# 467444_130_3_1.net
KiCad netlist of a schematic drawn in Altium Designer
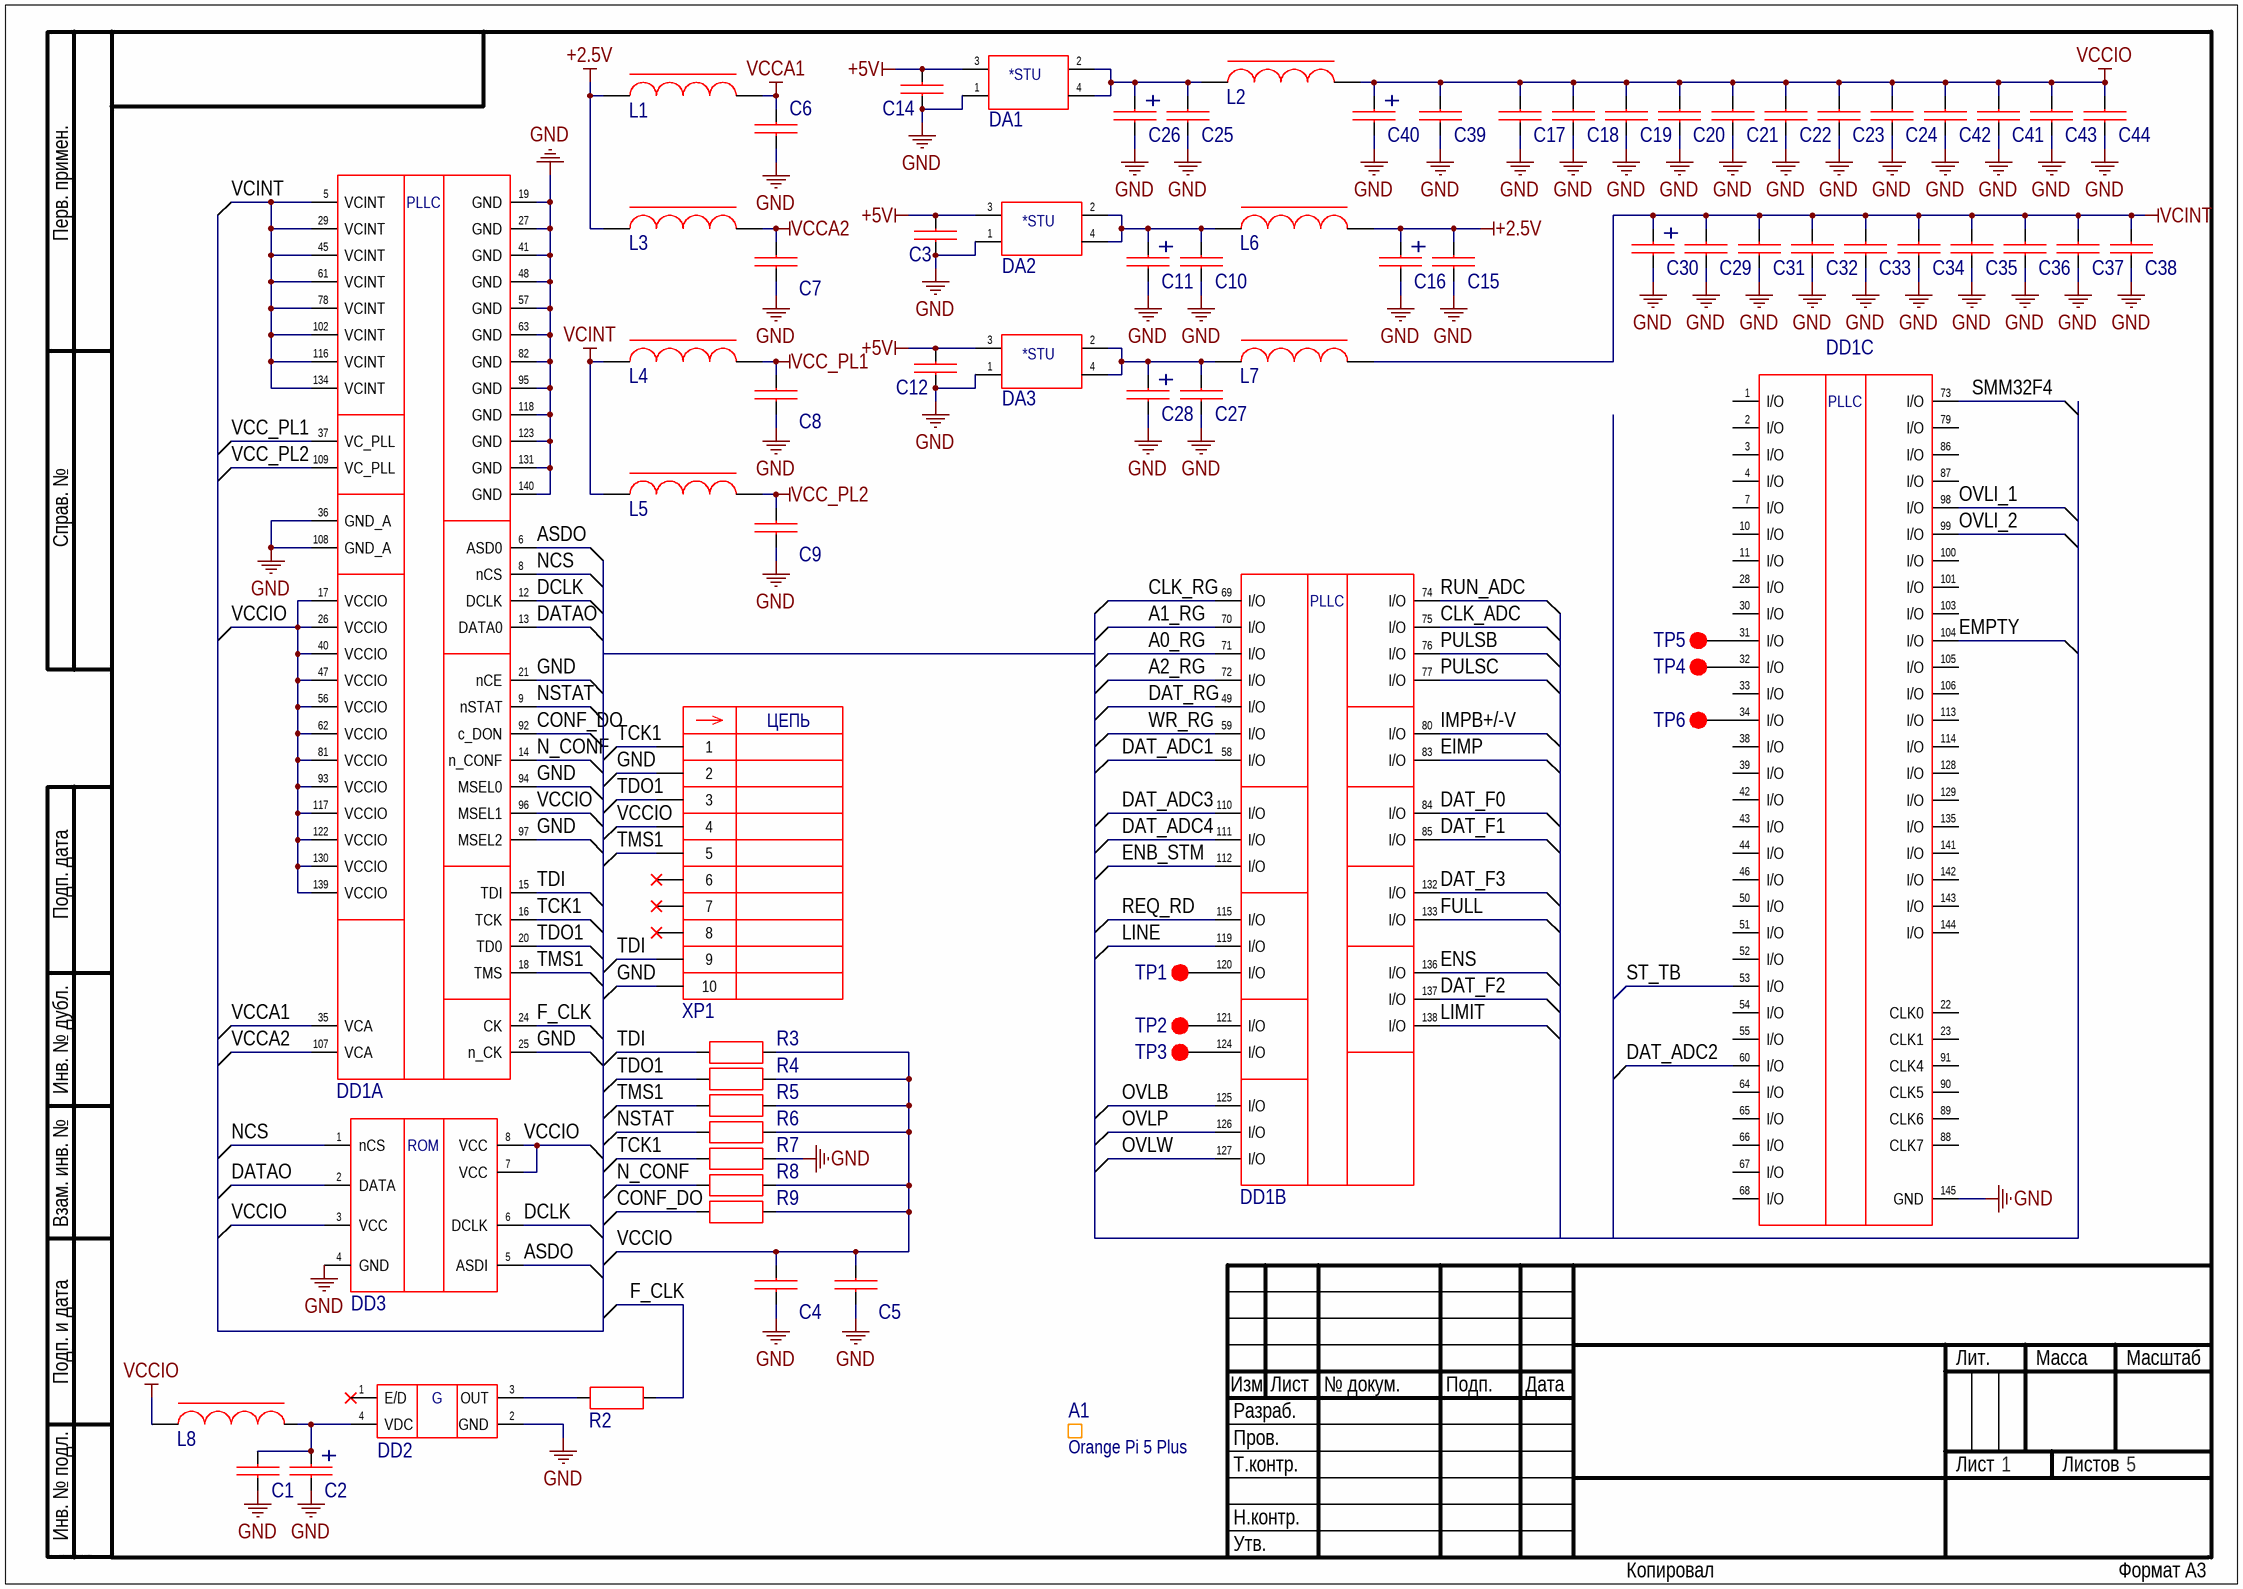
[diagram p0: УШЯИ.467444.130Э3_1.SchDoc]

(export (version "E")
  (design (tool "Eeschema 10.0.6"))
  (components
    (comp (ref "A1")
      (value "Orange Pi 5 Plus")
      (footprint "Orange_Pi_5_Plus")
      (description "8GB Rockchip RK3588, HDMI 2.1, Gigabit LAN port, USB2.0/3.0, microSD card slot, USB Type-C")
      (fields (field (name "MANUFACTURER") "Orange Pi"))
      (libsource (lib "lib") (part "0"))
    )
    (comp (ref "C1")
      (value "0,1 µF")
      (footprint "C_0805 [2012 Metric]")
      (description "Неполярный конденсатор")
      (fields (field (name "MANUFACTURER") "Murata") (field (name "VOLTAGE") "50V"))
      (libsource (lib "lib") (part "C_const"))
    )
    (comp (ref "C2")
      (value "4,7 µF")
      (footprint "C+_1210 [3528-21 Metric]")
      (description "Полярный конденсатор")
      (fields (field (name "MANUFACTURER") "KYOCERA AVX") (field (name "VOLTAGE") "20V\r\n10V"))
      (libsource (lib "lib") (part "C_electrolytic"))
    )
    (comp (ref "C3")
      (value "0,1 µF")
      (footprint "C_0805 [2012 Metric]")
      (description "Неполярный конденсатор")
      (fields (field (name "MANUFACTURER") "Murata") (field (name "VOLTAGE") "25V"))
      (libsource (lib "lib") (part "C_const"))
    )
    (comp (ref "C4")
      (value "1 µF")
      (footprint "C_0805 [2012 Metric]")
      (description "Неполярный конденсатор")
      (fields (field (name "MANUFACTURER") "Murata") (field (name "VOLTAGE") "16V"))
      (libsource (lib "lib") (part "C_const"))
    )
    (comp (ref "C5")
      (value "1 µF")
      (footprint "C_0805 [2012 Metric]")
      (description "Неполярный конденсатор")
      (fields (field (name "MANUFACTURER") "Murata") (field (name "VOLTAGE") "16V"))
      (libsource (lib "lib") (part "C_const"))
    )
    (comp (ref "C6")
      (value "0,1 µF")
      (footprint "C_0805 [2012 Metric]")
      (description "Неполярный конденсатор")
      (fields (field (name "MANUFACTURER") "Murata") (field (name "VOLTAGE") "25V"))
      (libsource (lib "lib") (part "C_const"))
    )
    (comp (ref "C7")
      (value "0,1 µF")
      (footprint "C_0805 [2012 Metric]")
      (description "Неполярный конденсатор")
      (fields (field (name "MANUFACTURER") "Murata") (field (name "VOLTAGE") "25V"))
      (libsource (lib "lib") (part "C_const"))
    )
    (comp (ref "C8")
      (value "0,1 µF")
      (footprint "C_0805 [2012 Metric]")
      (description "Неполярный конденсатор")
      (fields (field (name "MANUFACTURER") "Murata") (field (name "VOLTAGE") "25V"))
      (libsource (lib "lib") (part "C_const"))
    )
    (comp (ref "C9")
      (value "0,1 µF")
      (footprint "C_0805 [2012 Metric]")
      (description "Неполярный конденсатор")
      (fields (field (name "MANUFACTURER") "Murata") (field (name "VOLTAGE") "25V"))
      (libsource (lib "lib") (part "C_const"))
    )
    (comp (ref "C10")
      (value "0,1 µF")
      (footprint "C_0805 [2012 Metric]")
      (description "Неполярный конденсатор")
      (fields (field (name "MANUFACTURER") "Murata") (field (name "VOLTAGE") "25V"))
      (libsource (lib "lib") (part "C_const"))
    )
    (comp (ref "C11")
      (value "4,7 µF")
      (footprint "C+_1210 [3528-21 Metric]")
      (description "Полярный конденсатор")
      (fields (field (name "MANUFACTURER") "KYOCERA AVX") (field (name "VOLTAGE") "20V\r\n10V"))
      (libsource (lib "lib") (part "C_electrolytic"))
    )
    (comp (ref "C12")
      (value "0,1 µF")
      (footprint "C_0805 [2012 Metric]")
      (description "Неполярный конденсатор")
      (fields (field (name "MANUFACTURER") "Murata") (field (name "VOLTAGE") "25V"))
      (libsource (lib "lib") (part "C_const"))
    )
    (comp (ref "C14")
      (value "0,1 µF")
      (footprint "C_0805 [2012 Metric]")
      (description "Неполярный конденсатор")
      (fields (field (name "MANUFACTURER") "Murata") (field (name "VOLTAGE") "25V"))
      (libsource (lib "lib") (part "C_const"))
    )
    (comp (ref "C15")
      (value "0,1 µF")
      (footprint "C_0805 [2012 Metric]")
      (description "Неполярный конденсатор")
      (fields (field (name "MANUFACTURER") "Murata") (field (name "VOLTAGE") "25V"))
      (libsource (lib "lib") (part "C_const"))
    )
    (comp (ref "C16")
      (value "10 µF")
      (footprint "C+_1210 [3528-21 Metric]")
      (description "Полярный конденсатор")
      (fields (field (name "MANUFACTURER") "KYOCERA AVX") (field (name "VOLTAGE") "20V\r\n10V"))
      (libsource (lib "lib") (part "C_electrolytic"))
    )
    (comp (ref "C17")
      (value "0,1 µF")
      (footprint "C_0805 [2012 Metric]")
      (description "Неполярный конденсатор")
      (fields (field (name "MANUFACTURER") "Murata") (field (name "VOLTAGE") "25V"))
      (libsource (lib "lib") (part "C_const"))
    )
    (comp (ref "C18")
      (value "0,1 µF")
      (footprint "C_0805 [2012 Metric]")
      (description "Неполярный конденсатор")
      (fields (field (name "MANUFACTURER") "Murata") (field (name "VOLTAGE") "25V"))
      (libsource (lib "lib") (part "C_const"))
    )
    (comp (ref "C19")
      (value "0,1 µF")
      (footprint "C_0805 [2012 Metric]")
      (description "Неполярный конденсатор")
      (fields (field (name "MANUFACTURER") "Murata") (field (name "VOLTAGE") "25V"))
      (libsource (lib "lib") (part "C_const"))
    )
    (comp (ref "C20")
      (value "0,1 µF")
      (footprint "C_0805 [2012 Metric]")
      (description "Неполярный конденсатор")
      (fields (field (name "MANUFACTURER") "Murata") (field (name "VOLTAGE") "25V"))
      (libsource (lib "lib") (part "C_const"))
    )
    (comp (ref "C21")
      (value "0,1 µF")
      (footprint "C_0805 [2012 Metric]")
      (description "Неполярный конденсатор")
      (fields (field (name "MANUFACTURER") "Murata") (field (name "VOLTAGE") "25V"))
      (libsource (lib "lib") (part "C_const"))
    )
    (comp (ref "C22")
      (value "0,1 µF")
      (footprint "C_0805 [2012 Metric]")
      (description "Неполярный конденсатор")
      (fields (field (name "MANUFACTURER") "Murata") (field (name "VOLTAGE") "25V"))
      (libsource (lib "lib") (part "C_const"))
    )
    (comp (ref "C23")
      (value "0,1 µF")
      (footprint "C_0805 [2012 Metric]")
      (description "Неполярный конденсатор")
      (fields (field (name "MANUFACTURER") "Murata") (field (name "VOLTAGE") "25V"))
      (libsource (lib "lib") (part "C_const"))
    )
    (comp (ref "C24")
      (value "0,1 µF")
      (footprint "C_0805 [2012 Metric]")
      (description "Неполярный конденсатор")
      (fields (field (name "MANUFACTURER") "Murata") (field (name "VOLTAGE") "25V"))
      (libsource (lib "lib") (part "C_const"))
    )
    (comp (ref "C25")
      (value "0,1 µF")
      (footprint "C_0805 [2012 Metric]")
      (description "Неполярный конденсатор")
      (fields (field (name "MANUFACTURER") "Murata") (field (name "VOLTAGE") "25V"))
      (libsource (lib "lib") (part "C_const"))
    )
    (comp (ref "C26")
      (value "4,7 µF")
      (footprint "C+_1210 [3528-21 Metric]")
      (description "Полярный конденсатор")
      (fields (field (name "MANUFACTURER") "KYOCERA AVX") (field (name "VOLTAGE") "20V\r\n10V"))
      (libsource (lib "lib") (part "C_electrolytic"))
    )
    (comp (ref "C27")
      (value "0,1 µF")
      (footprint "C_0805 [2012 Metric]")
      (description "Неполярный конденсатор")
      (fields (field (name "MANUFACTURER") "Murata") (field (name "VOLTAGE") "50V"))
      (libsource (lib "lib") (part "C_const"))
    )
    (comp (ref "C28")
      (value "4,7 µF")
      (footprint "C+_1210 [3528-21 Metric]")
      (description "Полярный конденсатор")
      (fields (field (name "MANUFACTURER") "KYOCERA AVX") (field (name "VOLTAGE") "20V\r\n10V"))
      (libsource (lib "lib") (part "C_electrolytic"))
    )
    (comp (ref "C29")
      (value "0,1 µF")
      (footprint "C_0805 [2012 Metric]")
      (description "Неполярный конденсатор")
      (fields (field (name "MANUFACTURER") "Murata") (field (name "VOLTAGE") "50V"))
      (libsource (lib "lib") (part "C_const"))
    )
    (comp (ref "C30")
      (value "4,7 µF")
      (footprint "C+_1210 [3528-21 Metric]")
      (description "Полярный конденсатор")
      (fields (field (name "MANUFACTURER") "KYOCERA AVX") (field (name "VOLTAGE") "20V\r\n10V"))
      (libsource (lib "lib") (part "C_electrolytic"))
    )
    (comp (ref "C31")
      (value "0,1 µF")
      (footprint "C_0805 [2012 Metric]")
      (description "Неполярный конденсатор")
      (fields (field (name "MANUFACTURER") "Murata") (field (name "VOLTAGE") "50V"))
      (libsource (lib "lib") (part "C_const"))
    )
    (comp (ref "C32")
      (value "0,1 µF")
      (footprint "C_0805 [2012 Metric]")
      (description "Неполярный конденсатор")
      (fields (field (name "MANUFACTURER") "Murata") (field (name "VOLTAGE") "50V"))
      (libsource (lib "lib") (part "C_const"))
    )
    (comp (ref "C33")
      (value "0,1 µF")
      (footprint "C_0805 [2012 Metric]")
      (description "Неполярный конденсатор")
      (fields (field (name "MANUFACTURER") "Murata") (field (name "VOLTAGE") "50V"))
      (libsource (lib "lib") (part "C_const"))
    )
    (comp (ref "C34")
      (value "0,1 µF")
      (footprint "C_0805 [2012 Metric]")
      (description "Неполярный конденсатор")
      (fields (field (name "MANUFACTURER") "Murata") (field (name "VOLTAGE") "50V"))
      (libsource (lib "lib") (part "C_const"))
    )
    (comp (ref "C35")
      (value "0,1 µF")
      (footprint "C_0805 [2012 Metric]")
      (description "Неполярный конденсатор")
      (fields (field (name "MANUFACTURER") "Murata") (field (name "VOLTAGE") "50V"))
      (libsource (lib "lib") (part "C_const"))
    )
    (comp (ref "C36")
      (value "0,1 µF")
      (footprint "C_0805 [2012 Metric]")
      (description "Неполярный конденсатор")
      (fields (field (name "MANUFACTURER") "Murata") (field (name "VOLTAGE") "50V"))
      (libsource (lib "lib") (part "C_const"))
    )
    (comp (ref "C37")
      (value "0,1 µF")
      (footprint "C_0805 [2012 Metric]")
      (description "Неполярный конденсатор")
      (fields (field (name "MANUFACTURER") "Murata") (field (name "VOLTAGE") "50V"))
      (libsource (lib "lib") (part "C_const"))
    )
    (comp (ref "C38")
      (value "0,1 µF")
      (footprint "C_0805 [2012 Metric]")
      (description "Неполярный конденсатор")
      (fields (field (name "MANUFACTURER") "Murata") (field (name "VOLTAGE") "50V"))
      (libsource (lib "lib") (part "C_const"))
    )
    (comp (ref "C39")
      (value "0,1 µF")
      (footprint "C_0805 [2012 Metric]")
      (description "Неполярный конденсатор")
      (fields (field (name "MANUFACTURER") "Murata") (field (name "VOLTAGE") "50V"))
      (libsource (lib "lib") (part "C_const"))
    )
    (comp (ref "C40")
      (value "10 µF")
      (footprint "C+_1210 [3528-21 Metric]")
      (description "Полярный конденсатор")
      (fields (field (name "MANUFACTURER") "KYOCERA AVX") (field (name "VOLTAGE") "20V\r\n10V"))
      (libsource (lib "lib") (part "C_electrolytic"))
    )
    (comp (ref "C41")
      (value "0,1 µF")
      (footprint "C_0805 [2012 Metric]")
      (description "Неполярный конденсатор")
      (fields (field (name "MANUFACTURER") "Murata") (field (name "VOLTAGE") "50V"))
      (libsource (lib "lib") (part "C_const"))
    )
    (comp (ref "C42")
      (value "0,1 µF")
      (footprint "C_0805 [2012 Metric]")
      (description "Неполярный конденсатор")
      (fields (field (name "MANUFACTURER") "Murata") (field (name "VOLTAGE") "50V"))
      (libsource (lib "lib") (part "C_const"))
    )
    (comp (ref "C43")
      (value "0,1 µF")
      (footprint "C_0805 [2012 Metric]")
      (description "Неполярный конденсатор")
      (fields (field (name "MANUFACTURER") "Murata") (field (name "VOLTAGE") "50V"))
      (libsource (lib "lib") (part "C_const"))
    )
    (comp (ref "C44")
      (value "0,1 µF")
      (footprint "C_0805 [2012 Metric]")
      (description "Неполярный конденсатор")
      (fields (field (name "MANUFACTURER") "Murata") (field (name "VOLTAGE") "50V"))
      (libsource (lib "lib") (part "C_const"))
    )
    (comp (ref "DA1")
      (value "LD1117AS33TR")
      (footprint "SOT-223")
      (description "IC, Fixed LDO Voltage Regulator, 5.3V to 10V, 1.15V Dropout, 3.3Vout, 1Aout")
      (fields (field (name "MANUFACTURER") "STMicroelectronics"))
      (libsource (lib "lib") (part "VolReg_LD1117AS33TR"))
    )
    (comp (ref "DA2")
      (value "LD1117AS25TR")
      (footprint "SOT-223")
      (description "IC, Linear Voltage Regulator, 1 Output, 1V Dropout, 2.5Vout, 1Aout")
      (fields (field (name "MANUFACTURER") "STMicroelectronics"))
      (libsource (lib "lib") (part "VolReg_LD1117AS33TR"))
    )
    (comp (ref "DA3")
      (value "LD1117AS12TR")
      (footprint "SOT-223")
      (description "IC, Fixed LDO Voltage Regulator, 1 Output, 1V Dropout, 1.2Vout, 1Aout")
      (fields (field (name "MANUFACTURER") "STMicroelectronics"))
      (libsource (lib "lib") (part "VolReg_LD1117AS33TR"))
    )
    (comp (ref "DD1")
      (value "EP3C5E144I7")
      (footprint "EQFP-144[20x20]_0.5_22x22x1.6")
      (description "IC, Cyclone III, Field Programmable Gate Array (FPGA), 	1.15V to 1.25V, 315 MHz, 94 I/O")
      (fields (field (name "MANUFACTURER") "Intel"))
      (libsource (lib "lib") (part "EP3C5E144I7"))
    )
    (comp (ref "DD2")
      (value "O 20,0-JO32-B-3.3-1-T1-LF")
      (footprint "JO32")
      (description "Crystals, Oscillators, 20 MHz")
      (fields (field (name "MANUFACTURER") "Jauch Quartz GmbH"))
      (libsource (lib "lib") (part "JO32"))
    )
    (comp (ref "DD3")
      (value "EPCS4SI8N")
      (footprint "SOIC-8_1.27_5x4x1.75")
      (description "IC, FPGA Configuration Memory, Flash, 4 Mbit, 40 MHz, JTAG, Serial")
      (fields (field (name "MANUFACTURER") "Intel"))
      (libsource (lib "lib") (part "EPCS4"))
    )
    (comp (ref "L1")
      (value "0,22 μH")
      (footprint "IND_LQH31CN")
      (fields (field (name "MANUFACTURER") "Murata") (field (name "TOLERANCE") "±20%"))
      (libsource (lib "lib") (part "IND_ferromagnetic/ferrite_core"))
    )
    (comp (ref "L2")
      (value "~")
      (footprint "IND_0805 [2012 Metric]")
      (fields (field (name "MANUFACTURER") "Vishay") (field (name "TOLERANCE") "±25%"))
      (libsource (lib "lib") (part "IND_ferromagnetic/ferrite_core"))
    )
    (comp (ref "L3")
      (value "0,22 μH")
      (footprint "IND_LQH31CN")
      (fields (field (name "MANUFACTURER") "Murata") (field (name "TOLERANCE") "±20%"))
      (libsource (lib "lib") (part "IND_ferromagnetic/ferrite_core"))
    )
    (comp (ref "L4")
      (value "0,22 μH")
      (footprint "IND_LQH31CN")
      (fields (field (name "MANUFACTURER") "Murata") (field (name "TOLERANCE") "±20%"))
      (libsource (lib "lib") (part "IND_ferromagnetic/ferrite_core"))
    )
    (comp (ref "L5")
      (value "0,22 μH")
      (footprint "IND_LQH31CN")
      (fields (field (name "MANUFACTURER") "Murata") (field (name "TOLERANCE") "±20%"))
      (libsource (lib "lib") (part "IND_ferromagnetic/ferrite_core"))
    )
    (comp (ref "L6")
      (value "~")
      (footprint "IND_0805 [2012 Metric]")
      (fields (field (name "MANUFACTURER") "Vishay") (field (name "TOLERANCE") "±25%"))
      (libsource (lib "lib") (part "IND_ferromagnetic/ferrite_core"))
    )
    (comp (ref "L7")
      (value "~")
      (footprint "IND_0805 [2012 Metric]")
      (fields (field (name "MANUFACTURER") "Vishay") (field (name "TOLERANCE") "±25%"))
      (libsource (lib "lib") (part "IND_ferromagnetic/ferrite_core"))
    )
    (comp (ref "L8")
      (value "~")
      (footprint "IND_0805 [2012 Metric]")
      (fields (field (name "MANUFACTURER") "Vishay") (field (name "TOLERANCE") "±25%"))
      (libsource (lib "lib") (part "IND_ferromagnetic/ferrite_core"))
    )
    (comp (ref "R2")
      (value "51R")
      (footprint "R_0805 [2012 Metric]")
      (fields (field (name "TOLERANCE") "±5%"))
      (libsource (lib "lib") (part "R_Const"))
    )
    (comp (ref "R3")
      (value "1k")
      (footprint "R_0805 [2012 Metric]")
      (fields (field (name "TOLERANCE") "±5%"))
      (libsource (lib "lib") (part "R_Const"))
    )
    (comp (ref "R4")
      (value "10k")
      (footprint "R_0805 [2012 Metric]")
      (fields (field (name "TOLERANCE") "±5%"))
      (libsource (lib "lib") (part "R_Const"))
    )
    (comp (ref "R5")
      (value "1k")
      (footprint "R_0805 [2012 Metric]")
      (fields (field (name "TOLERANCE") "±5%"))
      (libsource (lib "lib") (part "R_Const"))
    )
    (comp (ref "R6")
      (value "10k")
      (footprint "R_0805 [2012 Metric]")
      (fields (field (name "TOLERANCE") "±5%"))
      (libsource (lib "lib") (part "R_Const"))
    )
    (comp (ref "R7")
      (value "1k")
      (footprint "R_0805 [2012 Metric]")
      (fields (field (name "TOLERANCE") "±5%"))
      (libsource (lib "lib") (part "R_Const"))
    )
    (comp (ref "R8")
      (value "10k")
      (footprint "R_0805 [2012 Metric]")
      (fields (field (name "TOLERANCE") "±5%"))
      (libsource (lib "lib") (part "R_Const"))
    )
    (comp (ref "R9")
      (value "10k")
      (footprint "R_0805 [2012 Metric]")
      (fields (field (name "TOLERANCE") "±5%"))
      (libsource (lib "lib") (part "R_Const"))
    )
    (comp (ref "TP1") (value "~") (footprint "DSP_1.3") (libsource (lib "lib") (part "TP")))
    (comp (ref "TP2") (value "~") (footprint "DSP_1.3") (libsource (lib "lib") (part "TP")))
    (comp (ref "TP3") (value "~") (footprint "DSP_1.3") (libsource (lib "lib") (part "TP")))
    (comp (ref "TP4") (value "~") (footprint "DSP_1.3") (libsource (lib "lib") (part "TP")))
    (comp (ref "TP5") (value "~") (footprint "DSP_1.3") (libsource (lib "lib") (part "TP")))
    (comp (ref "TP6") (value "~") (footprint "DSP_1.3") (libsource (lib "lib") (part "TP")))
    (comp (ref "XP1")
      (value "PLD-10")
      (footprint "PLD-10")
      (description "Male, 10 pins, 2 rows, Vertical")
      (fields (field (name "MANUFACTURER") "Connfly electronic"))
      (libsource (lib "lib") (part "M_10"))
    )
  )
  (nets
    (net (code "1") (name "+2.5V") (class "Default")
      (node (ref "C15") (pin "2") (pinfunction "2_2") (pintype "passive"))
      (node (ref "C16") (pin "+") (pinfunction "+_+") (pintype "passive"))
      (node (ref "L1") (pin "1") (pinfunction "1_1") (pintype "passive"))
      (node (ref "L3") (pin "1") (pinfunction "1_1") (pintype "passive"))
      (node (ref "L6") (pin "2") (pinfunction "2_2") (pintype "passive"))
    )
    (net (code "2") (name "+5V") (class "Default")
      (node (ref "C12") (pin "2") (pinfunction "2_2") (pintype "passive"))
      (node (ref "C14") (pin "2") (pinfunction "2_2") (pintype "passive"))
      (node (ref "C3") (pin "2") (pinfunction "2_2") (pintype "passive"))
      (node (ref "DA1") (pin "3") (pinfunction "VIN_3") (pintype "passive"))
      (node (ref "DA2") (pin "3") (pinfunction "VIN_3") (pintype "passive"))
      (node (ref "DA3") (pin "3") (pinfunction "VIN_3") (pintype "passive"))
    )
    (net (code "3") (name "/A0_RG") (class "Default")
      (node (ref "DD1") (pin "71") (pinfunction "I/O_71") (pintype "passive"))
    )
    (net (code "4") (name "/A1_RG") (class "Default")
      (node (ref "DD1") (pin "70") (pinfunction "I/O_70") (pintype "passive"))
    )
    (net (code "5") (name "/A2_RG") (class "Default")
      (node (ref "DD1") (pin "72") (pinfunction "I/O_72") (pintype "passive"))
    )
    (net (code "6") (name "/ASDO") (class "Default")
      (node (ref "DD1") (pin "6") (pinfunction "ASD0_6") (pintype "passive"))
      (node (ref "DD3") (pin "5") (pinfunction "ASDI_5") (pintype "passive"))
    )
    (net (code "7") (name "/CLK_ADC") (class "Default")
      (node (ref "DD1") (pin "75") (pinfunction "I/O_75") (pintype "passive"))
    )
    (net (code "8") (name "/CLK_RG") (class "Default")
      (node (ref "DD1") (pin "69") (pinfunction "I/O_69") (pintype "passive"))
    )
    (net (code "9") (name "/CONF_DO") (class "Default")
      (node (ref "DD1") (pin "92") (pinfunction "c_DON_92") (pintype "passive"))
      (node (ref "R9") (pin "1") (pinfunction "1_1") (pintype "passive"))
    )
    (net (code "10") (name "/DATAO") (class "Default")
      (node (ref "DD1") (pin "13") (pinfunction "DATA0_13") (pintype "passive"))
      (node (ref "DD3") (pin "2") (pinfunction "DATA_2") (pintype "passive"))
    )
    (net (code "11") (name "/DAT_ADC1") (class "Default")
      (node (ref "DD1") (pin "58") (pinfunction "I/O_58") (pintype "passive"))
    )
    (net (code "12") (name "/DAT_ADC2") (class "Default")
      (node (ref "DD1") (pin "60") (pinfunction "I/O_60") (pintype "passive"))
    )
    (net (code "13") (name "/DAT_ADC3") (class "Default")
      (node (ref "DD1") (pin "110") (pinfunction "I/O_110") (pintype "passive"))
    )
    (net (code "14") (name "/DAT_ADC4") (class "Default")
      (node (ref "DD1") (pin "111") (pinfunction "I/O_111") (pintype "passive"))
    )
    (net (code "15") (name "/DAT_F0") (class "Default")
      (node (ref "DD1") (pin "84") (pinfunction "I/O_84") (pintype "passive"))
    )
    (net (code "16") (name "/DAT_F1") (class "Default")
      (node (ref "DD1") (pin "85") (pinfunction "I/O_85") (pintype "passive"))
    )
    (net (code "17") (name "/DAT_F2") (class "Default")
      (node (ref "DD1") (pin "137") (pinfunction "I/O_137") (pintype "passive"))
    )
    (net (code "18") (name "/DAT_F3") (class "Default")
      (node (ref "DD1") (pin "132") (pinfunction "I/O_132") (pintype "passive"))
    )
    (net (code "19") (name "/DAT_RG") (class "Default")
      (node (ref "DD1") (pin "49") (pinfunction "I/O_49") (pintype "passive"))
    )
    (net (code "20") (name "/DCLK") (class "Default")
      (node (ref "DD1") (pin "12") (pinfunction "DCLK_12") (pintype "passive"))
      (node (ref "DD3") (pin "6") (pinfunction "DCLK_6") (pintype "passive"))
    )
    (net (code "21") (name "/EIMP") (class "Default")
      (node (ref "DD1") (pin "83") (pinfunction "I/O_83") (pintype "passive"))
    )
    (net (code "22") (name "/EMPTY") (class "Default")
      (node (ref "DD1") (pin "104") (pinfunction "I/O_104") (pintype "passive"))
    )
    (net (code "23") (name "/ENB_STM") (class "Default")
      (node (ref "DD1") (pin "112") (pinfunction "I/O_112") (pintype "passive"))
    )
    (net (code "24") (name "/ENS") (class "Default")
      (node (ref "DD1") (pin "136") (pinfunction "I/O_136") (pintype "passive"))
    )
    (net (code "25") (name "/FULL") (class "Default")
      (node (ref "DD1") (pin "133") (pinfunction "I/O_133") (pintype "passive"))
    )
    (net (code "26") (name "/F_CLK") (class "Default")
      (node (ref "DD1") (pin "24") (pinfunction "CK_24") (pintype "passive"))
      (node (ref "R2") (pin "2") (pinfunction "2_2") (pintype "passive"))
    )
    (net (code "27") (name "/IMPB+{slash}-V") (class "Default")
      (node (ref "DD1") (pin "80") (pinfunction "I/O_80") (pintype "passive"))
    )
    (net (code "28") (name "/LIMIT") (class "Default")
      (node (ref "DD1") (pin "138") (pinfunction "I/O_138") (pintype "passive"))
    )
    (net (code "29") (name "/LINE") (class "Default")
      (node (ref "DD1") (pin "119") (pinfunction "I/O_119") (pintype "passive"))
    )
    (net (code "30") (name "/NCS") (class "Default")
      (node (ref "DD1") (pin "8") (pinfunction "nCS_8") (pintype "passive"))
      (node (ref "DD3") (pin "1") (pinfunction "nCS_1") (pintype "passive"))
    )
    (net (code "31") (name "/NSTAT") (class "Default")
      (node (ref "DD1") (pin "9") (pinfunction "nSTAT_9") (pintype "passive"))
      (node (ref "R6") (pin "1") (pinfunction "1_1") (pintype "passive"))
    )
    (net (code "32") (name "/N_CONF") (class "Default")
      (node (ref "DD1") (pin "14") (pinfunction "n_CONF_14") (pintype "passive"))
      (node (ref "R8") (pin "1") (pinfunction "1_1") (pintype "passive"))
    )
    (net (code "33") (name "/OVLB") (class "Default")
      (node (ref "DD1") (pin "125") (pinfunction "I/O_125") (pintype "passive"))
    )
    (net (code "34") (name "/OVLI_1") (class "Default")
      (node (ref "DD1") (pin "98") (pinfunction "I/O_98") (pintype "passive"))
    )
    (net (code "35") (name "/OVLI_2") (class "Default")
      (node (ref "DD1") (pin "99") (pinfunction "I/O_99") (pintype "passive"))
    )
    (net (code "36") (name "/OVLP") (class "Default")
      (node (ref "DD1") (pin "126") (pinfunction "I/O_126") (pintype "passive"))
    )
    (net (code "37") (name "/OVLW") (class "Default")
      (node (ref "DD1") (pin "127") (pinfunction "I/O_127") (pintype "passive"))
    )
    (net (code "38") (name "/PULSB") (class "Default")
      (node (ref "DD1") (pin "76") (pinfunction "I/O_76") (pintype "passive"))
    )
    (net (code "39") (name "/PULSC") (class "Default")
      (node (ref "DD1") (pin "77") (pinfunction "I/O_77") (pintype "passive"))
    )
    (net (code "40") (name "/REQ_RD") (class "Default")
      (node (ref "DD1") (pin "115") (pinfunction "I/O_115") (pintype "passive"))
    )
    (net (code "41") (name "/RUN_ADC") (class "Default")
      (node (ref "DD1") (pin "74") (pinfunction "I/O_74") (pintype "passive"))
    )
    (net (code "42") (name "/SMM32F4") (class "Default")
      (node (ref "DD1") (pin "73") (pinfunction "I/O_73") (pintype "passive"))
    )
    (net (code "43") (name "/ST_TB") (class "Default")
      (node (ref "DD1") (pin "53") (pinfunction "I/O_53") (pintype "passive"))
    )
    (net (code "44") (name "/TCK1") (class "Default")
      (node (ref "DD1") (pin "16") (pinfunction "TCK_16") (pintype "passive"))
      (node (ref "R7") (pin "1") (pinfunction "1_1") (pintype "passive"))
      (node (ref "XP1") (pin "1") (pinfunction "1_1") (pintype "passive"))
    )
    (net (code "45") (name "/TDI") (class "Default")
      (node (ref "DD1") (pin "15") (pinfunction "TDI_15") (pintype "passive"))
      (node (ref "R3") (pin "1") (pinfunction "1_1") (pintype "passive"))
      (node (ref "XP1") (pin "9") (pinfunction "9_9") (pintype "passive"))
    )
    (net (code "46") (name "/TDO1") (class "Default")
      (node (ref "DD1") (pin "20") (pinfunction "TD0_20") (pintype "passive"))
      (node (ref "R4") (pin "1") (pinfunction "1_1") (pintype "passive"))
      (node (ref "XP1") (pin "3") (pinfunction "3_3") (pintype "passive"))
    )
    (net (code "47") (name "/TMS1") (class "Default")
      (node (ref "DD1") (pin "18") (pinfunction "TMS_18") (pintype "passive"))
      (node (ref "R5") (pin "1") (pinfunction "1_1") (pintype "passive"))
      (node (ref "XP1") (pin "5") (pinfunction "5_5") (pintype "passive"))
    )
    (net (code "48") (name "/WR_RG") (class "Default")
      (node (ref "DD1") (pin "59") (pinfunction "I/O_59") (pintype "passive"))
    )
    (net (code "49") (name "GND") (class "Default")
      (node (ref "C1") (pin "1") (pinfunction "1_1") (pintype "passive"))
      (node (ref "C10") (pin "1") (pinfunction "1_1") (pintype "passive"))
      (node (ref "C11") (pin "-") (pinfunction "-_-") (pintype "passive"))
      (node (ref "C12") (pin "1") (pinfunction "1_1") (pintype "passive"))
      (node (ref "C14") (pin "1") (pinfunction "1_1") (pintype "passive"))
      (node (ref "C15") (pin "1") (pinfunction "1_1") (pintype "passive"))
      (node (ref "C16") (pin "-") (pinfunction "-_-") (pintype "passive"))
      (node (ref "C17") (pin "1") (pinfunction "1_1") (pintype "passive"))
      (node (ref "C18") (pin "1") (pinfunction "1_1") (pintype "passive"))
      (node (ref "C19") (pin "1") (pinfunction "1_1") (pintype "passive"))
      (node (ref "C2") (pin "-") (pinfunction "-_-") (pintype "passive"))
      (node (ref "C20") (pin "1") (pinfunction "1_1") (pintype "passive"))
      (node (ref "C21") (pin "1") (pinfunction "1_1") (pintype "passive"))
      (node (ref "C22") (pin "1") (pinfunction "1_1") (pintype "passive"))
      (node (ref "C23") (pin "1") (pinfunction "1_1") (pintype "passive"))
      (node (ref "C24") (pin "1") (pinfunction "1_1") (pintype "passive"))
      (node (ref "C25") (pin "1") (pinfunction "1_1") (pintype "passive"))
      (node (ref "C26") (pin "-") (pinfunction "-_-") (pintype "passive"))
      (node (ref "C27") (pin "1") (pinfunction "1_1") (pintype "passive"))
      (node (ref "C28") (pin "-") (pinfunction "-_-") (pintype "passive"))
      (node (ref "C29") (pin "1") (pinfunction "1_1") (pintype "passive"))
      (node (ref "C3") (pin "1") (pinfunction "1_1") (pintype "passive"))
      (node (ref "C30") (pin "-") (pinfunction "-_-") (pintype "passive"))
      (node (ref "C31") (pin "1") (pinfunction "1_1") (pintype "passive"))
      (node (ref "C32") (pin "1") (pinfunction "1_1") (pintype "passive"))
      (node (ref "C33") (pin "1") (pinfunction "1_1") (pintype "passive"))
      (node (ref "C34") (pin "1") (pinfunction "1_1") (pintype "passive"))
      (node (ref "C35") (pin "1") (pinfunction "1_1") (pintype "passive"))
      (node (ref "C36") (pin "1") (pinfunction "1_1") (pintype "passive"))
      (node (ref "C37") (pin "1") (pinfunction "1_1") (pintype "passive"))
      (node (ref "C38") (pin "1") (pinfunction "1_1") (pintype "passive"))
      (node (ref "C39") (pin "1") (pinfunction "1_1") (pintype "passive"))
      (node (ref "C4") (pin "1") (pinfunction "1_1") (pintype "passive"))
      (node (ref "C40") (pin "-") (pinfunction "-_-") (pintype "passive"))
      (node (ref "C41") (pin "1") (pinfunction "1_1") (pintype "passive"))
      (node (ref "C42") (pin "1") (pinfunction "1_1") (pintype "passive"))
      (node (ref "C43") (pin "1") (pinfunction "1_1") (pintype "passive"))
      (node (ref "C44") (pin "1") (pinfunction "1_1") (pintype "passive"))
      (node (ref "C5") (pin "1") (pinfunction "1_1") (pintype "passive"))
      (node (ref "C6") (pin "1") (pinfunction "1_1") (pintype "passive"))
      (node (ref "C7") (pin "1") (pinfunction "1_1") (pintype "passive"))
      (node (ref "C8") (pin "1") (pinfunction "1_1") (pintype "passive"))
      (node (ref "C9") (pin "1") (pinfunction "1_1") (pintype "passive"))
      (node (ref "DA1") (pin "1") (pinfunction "ADJ/GND_1") (pintype "passive"))
      (node (ref "DA2") (pin "1") (pinfunction "ADJ/GND_1") (pintype "passive"))
      (node (ref "DA3") (pin "1") (pinfunction "ADJ/GND_1") (pintype "passive"))
      (node (ref "DD1") (pin "108") (pinfunction "GND_A_108") (pintype "passive"))
      (node (ref "DD1") (pin "118") (pinfunction "GND_118") (pintype "passive"))
      (node (ref "DD1") (pin "123") (pinfunction "GND_123") (pintype "passive"))
      (node (ref "DD1") (pin "131") (pinfunction "GND_131") (pintype "passive"))
      (node (ref "DD1") (pin "140") (pinfunction "GND_140") (pintype "passive"))
      (node (ref "DD1") (pin "145") (pinfunction "GND_145") (pintype "passive"))
      (node (ref "DD1") (pin "19") (pinfunction "GND_19") (pintype "passive"))
      (node (ref "DD1") (pin "21") (pinfunction "nCE_21") (pintype "passive"))
      (node (ref "DD1") (pin "25") (pinfunction "n_CK_25") (pintype "passive"))
      (node (ref "DD1") (pin "27") (pinfunction "GND_27") (pintype "passive"))
      (node (ref "DD1") (pin "36") (pinfunction "GND_A_36") (pintype "passive"))
      (node (ref "DD1") (pin "41") (pinfunction "GND_41") (pintype "passive"))
      (node (ref "DD1") (pin "48") (pinfunction "GND_48") (pintype "passive"))
      (node (ref "DD1") (pin "57") (pinfunction "GND_57") (pintype "passive"))
      (node (ref "DD1") (pin "63") (pinfunction "GND_63") (pintype "passive"))
      (node (ref "DD1") (pin "82") (pinfunction "GND_82") (pintype "passive"))
      (node (ref "DD1") (pin "94") (pinfunction "MSEL0_94") (pintype "passive"))
      (node (ref "DD1") (pin "95") (pinfunction "GND_95") (pintype "passive"))
      (node (ref "DD1") (pin "97") (pinfunction "MSEL2_97") (pintype "passive"))
      (node (ref "DD2") (pin "2") (pinfunction "GND_2") (pintype "passive"))
      (node (ref "DD3") (pin "4") (pinfunction "GND_4") (pintype "passive"))
      (node (ref "R7") (pin "2") (pinfunction "2_2") (pintype "passive"))
      (node (ref "XP1") (pin "10") (pinfunction "10_10") (pintype "passive"))
      (node (ref "XP1") (pin "2") (pinfunction "2_2") (pintype "passive"))
    )
    (net (code "50") (name "Net-(C10-Pad2)") (class "Default")
      (node (ref "C10") (pin "2") (pinfunction "2_2") (pintype "passive"))
      (node (ref "C11") (pin "+") (pinfunction "+_+") (pintype "passive"))
      (node (ref "DA2") (pin "2") (pinfunction "VOUT_2") (pintype "passive"))
      (node (ref "DA2") (pin "4") (pinfunction "VOUT_4") (pintype "passive"))
      (node (ref "L6") (pin "1") (pinfunction "1_1") (pintype "passive"))
    )
    (net (code "51") (name "Net-(C25-Pad2)") (class "Default")
      (node (ref "C25") (pin "2") (pinfunction "2_2") (pintype "passive"))
      (node (ref "C26") (pin "+") (pinfunction "+_+") (pintype "passive"))
      (node (ref "DA1") (pin "2") (pinfunction "VOUT_2") (pintype "passive"))
      (node (ref "DA1") (pin "4") (pinfunction "VOUT_4") (pintype "passive"))
      (node (ref "L2") (pin "1") (pinfunction "1_1") (pintype "passive"))
    )
    (net (code "52") (name "Net-(C27-Pad2)") (class "Default")
      (node (ref "C27") (pin "2") (pinfunction "2_2") (pintype "passive"))
      (node (ref "C28") (pin "+") (pinfunction "+_+") (pintype "passive"))
      (node (ref "DA3") (pin "2") (pinfunction "VOUT_2") (pintype "passive"))
      (node (ref "DA3") (pin "4") (pinfunction "VOUT_4") (pintype "passive"))
      (node (ref "L7") (pin "1") (pinfunction "1_1") (pintype "passive"))
    )
    (net (code "53") (name "Net-(DD1B-I{slash}O-Pad120)") (class "Default")
      (node (ref "DD1") (pin "120") (pinfunction "I/O_120") (pintype "passive"))
      (node (ref "TP1") (pin "1") (pinfunction "1_1") (pintype "passive"))
    )
    (net (code "54") (name "Net-(DD1B-I{slash}O-Pad121)") (class "Default")
      (node (ref "DD1") (pin "121") (pinfunction "I/O_121") (pintype "passive"))
      (node (ref "TP2") (pin "1") (pinfunction "1_1") (pintype "passive"))
    )
    (net (code "55") (name "Net-(DD1B-I{slash}O-Pad124)") (class "Default")
      (node (ref "DD1") (pin "124") (pinfunction "I/O_124") (pintype "passive"))
      (node (ref "TP3") (pin "1") (pinfunction "1_1") (pintype "passive"))
    )
    (net (code "56") (name "Net-(DD1C-I{slash}O-Pad31)") (class "Default")
      (node (ref "DD1") (pin "31") (pinfunction "I/O_31") (pintype "passive"))
      (node (ref "TP5") (pin "1") (pinfunction "1_1") (pintype "passive"))
    )
    (net (code "57") (name "Net-(DD1C-I{slash}O-Pad32)") (class "Default")
      (node (ref "DD1") (pin "32") (pinfunction "I/O_32") (pintype "passive"))
      (node (ref "TP4") (pin "1") (pinfunction "1_1") (pintype "passive"))
    )
    (net (code "58") (name "Net-(DD1C-I{slash}O-Pad34)") (class "Default")
      (node (ref "DD1") (pin "34") (pinfunction "I/O_34") (pintype "passive"))
      (node (ref "TP6") (pin "1") (pinfunction "1_1") (pintype "passive"))
    )
    (net (code "59") (name "Net-(DD2-OUT)") (class "Default")
      (node (ref "DD2") (pin "3") (pinfunction "OUT_3") (pintype "passive"))
      (node (ref "R2") (pin "1") (pinfunction "1_1") (pintype "passive"))
    )
    (net (code "60") (name "Net-(DD2-VDC)") (class "Default")
      (node (ref "C1") (pin "2") (pinfunction "2_2") (pintype "passive"))
      (node (ref "C2") (pin "+") (pinfunction "+_+") (pintype "passive"))
      (node (ref "DD2") (pin "4") (pinfunction "VDC_4") (pintype "passive"))
      (node (ref "L8") (pin "2") (pinfunction "2_2") (pintype "passive"))
    )
    (net (code "61") (name "VCCA1") (class "Default")
      (node (ref "C6") (pin "2") (pinfunction "2_2") (pintype "passive"))
      (node (ref "DD1") (pin "35") (pinfunction "VCA_35") (pintype "passive"))
      (node (ref "L1") (pin "2") (pinfunction "2_2") (pintype "passive"))
    )
    (net (code "62") (name "VCCA2") (class "Default")
      (node (ref "C7") (pin "2") (pinfunction "2_2") (pintype "passive"))
      (node (ref "DD1") (pin "107") (pinfunction "VCA_107") (pintype "passive"))
      (node (ref "L3") (pin "2") (pinfunction "2_2") (pintype "passive"))
    )
    (net (code "63") (name "VCCIO") (class "Default")
      (node (ref "C17") (pin "2") (pinfunction "2_2") (pintype "passive"))
      (node (ref "C18") (pin "2") (pinfunction "2_2") (pintype "passive"))
      (node (ref "C19") (pin "2") (pinfunction "2_2") (pintype "passive"))
      (node (ref "C20") (pin "2") (pinfunction "2_2") (pintype "passive"))
      (node (ref "C21") (pin "2") (pinfunction "2_2") (pintype "passive"))
      (node (ref "C22") (pin "2") (pinfunction "2_2") (pintype "passive"))
      (node (ref "C23") (pin "2") (pinfunction "2_2") (pintype "passive"))
      (node (ref "C24") (pin "2") (pinfunction "2_2") (pintype "passive"))
      (node (ref "C39") (pin "2") (pinfunction "2_2") (pintype "passive"))
      (node (ref "C4") (pin "2") (pinfunction "2_2") (pintype "passive"))
      (node (ref "C40") (pin "+") (pinfunction "+_+") (pintype "passive"))
      (node (ref "C41") (pin "2") (pinfunction "2_2") (pintype "passive"))
      (node (ref "C42") (pin "2") (pinfunction "2_2") (pintype "passive"))
      (node (ref "C43") (pin "2") (pinfunction "2_2") (pintype "passive"))
      (node (ref "C44") (pin "2") (pinfunction "2_2") (pintype "passive"))
      (node (ref "C5") (pin "2") (pinfunction "2_2") (pintype "passive"))
      (node (ref "DD1") (pin "117") (pinfunction "VCCIO_117") (pintype "passive"))
      (node (ref "DD1") (pin "122") (pinfunction "VCCIO_122") (pintype "passive"))
      (node (ref "DD1") (pin "130") (pinfunction "VCCIO_130") (pintype "passive"))
      (node (ref "DD1") (pin "139") (pinfunction "VCCIO_139") (pintype "passive"))
      (node (ref "DD1") (pin "17") (pinfunction "VCCIO_17") (pintype "passive"))
      (node (ref "DD1") (pin "26") (pinfunction "VCCIO_26") (pintype "passive"))
      (node (ref "DD1") (pin "40") (pinfunction "VCCIO_40") (pintype "passive"))
      (node (ref "DD1") (pin "47") (pinfunction "VCCIO_47") (pintype "passive"))
      (node (ref "DD1") (pin "56") (pinfunction "VCCIO_56") (pintype "passive"))
      (node (ref "DD1") (pin "62") (pinfunction "VCCIO_62") (pintype "passive"))
      (node (ref "DD1") (pin "81") (pinfunction "VCCIO_81") (pintype "passive"))
      (node (ref "DD1") (pin "93") (pinfunction "VCCIO_93") (pintype "passive"))
      (node (ref "DD1") (pin "96") (pinfunction "MSEL1_96") (pintype "passive"))
      (node (ref "DD3") (pin "3") (pinfunction "VCC_3") (pintype "passive"))
      (node (ref "DD3") (pin "7") (pinfunction "VCC_7") (pintype "passive"))
      (node (ref "DD3") (pin "8") (pinfunction "VCC_8") (pintype "passive"))
      (node (ref "L2") (pin "2") (pinfunction "2_2") (pintype "passive"))
      (node (ref "L8") (pin "1") (pinfunction "1_1") (pintype "passive"))
      (node (ref "R3") (pin "2") (pinfunction "2_2") (pintype "passive"))
      (node (ref "R4") (pin "2") (pinfunction "2_2") (pintype "passive"))
      (node (ref "R5") (pin "2") (pinfunction "2_2") (pintype "passive"))
      (node (ref "R6") (pin "2") (pinfunction "2_2") (pintype "passive"))
      (node (ref "R8") (pin "2") (pinfunction "2_2") (pintype "passive"))
      (node (ref "R9") (pin "2") (pinfunction "2_2") (pintype "passive"))
      (node (ref "XP1") (pin "4") (pinfunction "4_4") (pintype "passive"))
    )
    (net (code "64") (name "VCC_PL1") (class "Default")
      (node (ref "C8") (pin "2") (pinfunction "2_2") (pintype "passive"))
      (node (ref "DD1") (pin "37") (pinfunction "VC_PLL_37") (pintype "passive"))
      (node (ref "L4") (pin "2") (pinfunction "2_2") (pintype "passive"))
    )
    (net (code "65") (name "VCC_PL2") (class "Default")
      (node (ref "C9") (pin "2") (pinfunction "2_2") (pintype "passive"))
      (node (ref "DD1") (pin "109") (pinfunction "VC_PLL_109") (pintype "passive"))
      (node (ref "L5") (pin "2") (pinfunction "2_2") (pintype "passive"))
    )
    (net (code "66") (name "VCINT") (class "Default")
      (node (ref "C29") (pin "2") (pinfunction "2_2") (pintype "passive"))
      (node (ref "C30") (pin "+") (pinfunction "+_+") (pintype "passive"))
      (node (ref "C31") (pin "2") (pinfunction "2_2") (pintype "passive"))
      (node (ref "C32") (pin "2") (pinfunction "2_2") (pintype "passive"))
      (node (ref "C33") (pin "2") (pinfunction "2_2") (pintype "passive"))
      (node (ref "C34") (pin "2") (pinfunction "2_2") (pintype "passive"))
      (node (ref "C35") (pin "2") (pinfunction "2_2") (pintype "passive"))
      (node (ref "C36") (pin "2") (pinfunction "2_2") (pintype "passive"))
      (node (ref "C37") (pin "2") (pinfunction "2_2") (pintype "passive"))
      (node (ref "C38") (pin "2") (pinfunction "2_2") (pintype "passive"))
      (node (ref "DD1") (pin "102") (pinfunction "VCINT_102") (pintype "passive"))
      (node (ref "DD1") (pin "116") (pinfunction "VCINT_116") (pintype "passive"))
      (node (ref "DD1") (pin "134") (pinfunction "VCINT_134") (pintype "passive"))
      (node (ref "DD1") (pin "29") (pinfunction "VCINT_29") (pintype "passive"))
      (node (ref "DD1") (pin "45") (pinfunction "VCINT_45") (pintype "passive"))
      (node (ref "DD1") (pin "5") (pinfunction "VCINT_5") (pintype "passive"))
      (node (ref "DD1") (pin "61") (pinfunction "VCINT_61") (pintype "passive"))
      (node (ref "DD1") (pin "78") (pinfunction "VCINT_78") (pintype "passive"))
      (node (ref "L4") (pin "1") (pinfunction "1_1") (pintype "passive"))
      (node (ref "L5") (pin "1") (pinfunction "1_1") (pintype "passive"))
      (node (ref "L7") (pin "2") (pinfunction "2_2") (pintype "passive"))
    )
    (net (code "67") (name "unconnected-(DD1C-CLK0-Pad22)") (class "Default")
      (node (ref "DD1") (pin "22") (pinfunction "CLK0_22") (pintype "passive"))
    )
    (net (code "68") (name "unconnected-(DD1C-CLK1-Pad23)") (class "Default")
      (node (ref "DD1") (pin "23") (pinfunction "CLK1_23") (pintype "passive"))
    )
    (net (code "69") (name "unconnected-(DD1C-CLK4-Pad91)") (class "Default")
      (node (ref "DD1") (pin "91") (pinfunction "CLK4_91") (pintype "passive"))
    )
    (net (code "70") (name "unconnected-(DD1C-CLK5-Pad90)") (class "Default")
      (node (ref "DD1") (pin "90") (pinfunction "CLK5_90") (pintype "passive"))
    )
    (net (code "71") (name "unconnected-(DD1C-CLK6-Pad89)") (class "Default")
      (node (ref "DD1") (pin "89") (pinfunction "CLK6_89") (pintype "passive"))
    )
    (net (code "72") (name "unconnected-(DD1C-CLK7-Pad88)") (class "Default")
      (node (ref "DD1") (pin "88") (pinfunction "CLK7_88") (pintype "passive"))
    )
    (net (code "73") (name "unconnected-(DD1C-I{slash}O-Pad1)") (class "Default")
      (node (ref "DD1") (pin "1") (pinfunction "I/O_1") (pintype "passive"))
    )
    (net (code "74") (name "unconnected-(DD1C-I{slash}O-Pad2)") (class "Default")
      (node (ref "DD1") (pin "2") (pinfunction "I/O_2") (pintype "passive"))
    )
    (net (code "75") (name "unconnected-(DD1C-I{slash}O-Pad3)") (class "Default")
      (node (ref "DD1") (pin "3") (pinfunction "I/O_3") (pintype "passive"))
    )
    (net (code "76") (name "unconnected-(DD1C-I{slash}O-Pad4)") (class "Default")
      (node (ref "DD1") (pin "4") (pinfunction "I/O_4") (pintype "passive"))
    )
    (net (code "77") (name "unconnected-(DD1C-I{slash}O-Pad7)") (class "Default")
      (node (ref "DD1") (pin "7") (pinfunction "I/O_7") (pintype "passive"))
    )
    (net (code "78") (name "unconnected-(DD1C-I{slash}O-Pad10)") (class "Default")
      (node (ref "DD1") (pin "10") (pinfunction "I/O_10") (pintype "passive"))
    )
    (net (code "79") (name "unconnected-(DD1C-I{slash}O-Pad11)") (class "Default")
      (node (ref "DD1") (pin "11") (pinfunction "I/O_11") (pintype "passive"))
    )
    (net (code "80") (name "unconnected-(DD1C-I{slash}O-Pad28)") (class "Default")
      (node (ref "DD1") (pin "28") (pinfunction "I/O_28") (pintype "passive"))
    )
    (net (code "81") (name "unconnected-(DD1C-I{slash}O-Pad30)") (class "Default")
      (node (ref "DD1") (pin "30") (pinfunction "I/O_30") (pintype "passive"))
    )
    (net (code "82") (name "unconnected-(DD1C-I{slash}O-Pad33)") (class "Default")
      (node (ref "DD1") (pin "33") (pinfunction "I/O_33") (pintype "passive"))
    )
    (net (code "83") (name "unconnected-(DD1C-I{slash}O-Pad38)") (class "Default")
      (node (ref "DD1") (pin "38") (pinfunction "I/O_38") (pintype "passive"))
    )
    (net (code "84") (name "unconnected-(DD1C-I{slash}O-Pad39)") (class "Default")
      (node (ref "DD1") (pin "39") (pinfunction "I/O_39") (pintype "passive"))
    )
    (net (code "85") (name "unconnected-(DD1C-I{slash}O-Pad42)") (class "Default")
      (node (ref "DD1") (pin "42") (pinfunction "I/O_42") (pintype "passive"))
    )
    (net (code "86") (name "unconnected-(DD1C-I{slash}O-Pad43)") (class "Default")
      (node (ref "DD1") (pin "43") (pinfunction "I/O_43") (pintype "passive"))
    )
    (net (code "87") (name "unconnected-(DD1C-I{slash}O-Pad44)") (class "Default")
      (node (ref "DD1") (pin "44") (pinfunction "I/O_44") (pintype "passive"))
    )
    (net (code "88") (name "unconnected-(DD1C-I{slash}O-Pad46)") (class "Default")
      (node (ref "DD1") (pin "46") (pinfunction "I/O_46") (pintype "passive"))
    )
    (net (code "89") (name "unconnected-(DD1C-I{slash}O-Pad50)") (class "Default")
      (node (ref "DD1") (pin "50") (pinfunction "I/O_50") (pintype "passive"))
    )
    (net (code "90") (name "unconnected-(DD1C-I{slash}O-Pad51)") (class "Default")
      (node (ref "DD1") (pin "51") (pinfunction "I/O_51") (pintype "passive"))
    )
    (net (code "91") (name "unconnected-(DD1C-I{slash}O-Pad52)") (class "Default")
      (node (ref "DD1") (pin "52") (pinfunction "I/O_52") (pintype "passive"))
    )
    (net (code "92") (name "unconnected-(DD1C-I{slash}O-Pad54)") (class "Default")
      (node (ref "DD1") (pin "54") (pinfunction "I/O_54") (pintype "passive"))
    )
    (net (code "93") (name "unconnected-(DD1C-I{slash}O-Pad55)") (class "Default")
      (node (ref "DD1") (pin "55") (pinfunction "I/O_55") (pintype "passive"))
    )
    (net (code "94") (name "unconnected-(DD1C-I{slash}O-Pad64)") (class "Default")
      (node (ref "DD1") (pin "64") (pinfunction "I/O_64") (pintype "passive"))
    )
    (net (code "95") (name "unconnected-(DD1C-I{slash}O-Pad65)") (class "Default")
      (node (ref "DD1") (pin "65") (pinfunction "I/O_65") (pintype "passive"))
    )
    (net (code "96") (name "unconnected-(DD1C-I{slash}O-Pad66)") (class "Default")
      (node (ref "DD1") (pin "66") (pinfunction "I/O_66") (pintype "passive"))
    )
    (net (code "97") (name "unconnected-(DD1C-I{slash}O-Pad67)") (class "Default")
      (node (ref "DD1") (pin "67") (pinfunction "I/O_67") (pintype "passive"))
    )
    (net (code "98") (name "unconnected-(DD1C-I{slash}O-Pad68)") (class "Default")
      (node (ref "DD1") (pin "68") (pinfunction "I/O_68") (pintype "passive"))
    )
    (net (code "99") (name "unconnected-(DD1C-I{slash}O-Pad79)") (class "Default")
      (node (ref "DD1") (pin "79") (pinfunction "I/O_79") (pintype "passive"))
    )
    (net (code "100") (name "unconnected-(DD1C-I{slash}O-Pad86)") (class "Default")
      (node (ref "DD1") (pin "86") (pinfunction "I/O_86") (pintype "passive"))
    )
    (net (code "101") (name "unconnected-(DD1C-I{slash}O-Pad87)") (class "Default")
      (node (ref "DD1") (pin "87") (pinfunction "I/O_87") (pintype "passive"))
    )
    (net (code "102") (name "unconnected-(DD1C-I{slash}O-Pad100)") (class "Default")
      (node (ref "DD1") (pin "100") (pinfunction "I/O_100") (pintype "passive"))
    )
    (net (code "103") (name "unconnected-(DD1C-I{slash}O-Pad101)") (class "Default")
      (node (ref "DD1") (pin "101") (pinfunction "I/O_101") (pintype "passive"))
    )
    (net (code "104") (name "unconnected-(DD1C-I{slash}O-Pad103)") (class "Default")
      (node (ref "DD1") (pin "103") (pinfunction "I/O_103") (pintype "passive"))
    )
    (net (code "105") (name "unconnected-(DD1C-I{slash}O-Pad105)") (class "Default")
      (node (ref "DD1") (pin "105") (pinfunction "I/O_105") (pintype "passive"))
    )
    (net (code "106") (name "unconnected-(DD1C-I{slash}O-Pad106)") (class "Default")
      (node (ref "DD1") (pin "106") (pinfunction "I/O_106") (pintype "passive"))
    )
    (net (code "107") (name "unconnected-(DD1C-I{slash}O-Pad113)") (class "Default")
      (node (ref "DD1") (pin "113") (pinfunction "I/O_113") (pintype "passive"))
    )
    (net (code "108") (name "unconnected-(DD1C-I{slash}O-Pad114)") (class "Default")
      (node (ref "DD1") (pin "114") (pinfunction "I/O_114") (pintype "passive"))
    )
    (net (code "109") (name "unconnected-(DD1C-I{slash}O-Pad128)") (class "Default")
      (node (ref "DD1") (pin "128") (pinfunction "I/O_128") (pintype "passive"))
    )
    (net (code "110") (name "unconnected-(DD1C-I{slash}O-Pad129)") (class "Default")
      (node (ref "DD1") (pin "129") (pinfunction "I/O_129") (pintype "passive"))
    )
    (net (code "111") (name "unconnected-(DD1C-I{slash}O-Pad135)") (class "Default")
      (node (ref "DD1") (pin "135") (pinfunction "I/O_135") (pintype "passive"))
    )
    (net (code "112") (name "unconnected-(DD1C-I{slash}O-Pad141)") (class "Default")
      (node (ref "DD1") (pin "141") (pinfunction "I/O_141") (pintype "passive"))
    )
    (net (code "113") (name "unconnected-(DD1C-I{slash}O-Pad142)") (class "Default")
      (node (ref "DD1") (pin "142") (pinfunction "I/O_142") (pintype "passive"))
    )
    (net (code "114") (name "unconnected-(DD1C-I{slash}O-Pad143)") (class "Default")
      (node (ref "DD1") (pin "143") (pinfunction "I/O_143") (pintype "passive"))
    )
    (net (code "115") (name "unconnected-(DD1C-I{slash}O-Pad144)") (class "Default")
      (node (ref "DD1") (pin "144") (pinfunction "I/O_144") (pintype "passive"))
    )
    (net (code "116") (name "unconnected-(DD2-E{slash}D-Pad1)") (class "Default")
      (node (ref "DD2") (pin "1") (pinfunction "E/D_1") (pintype "passive+no_connect"))
    )
    (net (code "117") (name "unconnected-(XP1-Pad6)") (class "Default")
      (node (ref "XP1") (pin "6") (pinfunction "6_6") (pintype "passive+no_connect"))
    )
    (net (code "118") (name "unconnected-(XP1-Pad7)") (class "Default")
      (node (ref "XP1") (pin "7") (pinfunction "7_7") (pintype "passive+no_connect"))
    )
    (net (code "119") (name "unconnected-(XP1-Pad8)") (class "Default")
      (node (ref "XP1") (pin "8") (pinfunction "8_8") (pintype "passive+no_connect"))
    )
  )
)
